# single_LED_driver.net
KiCad netlist of a schematic drawn in EAGLE
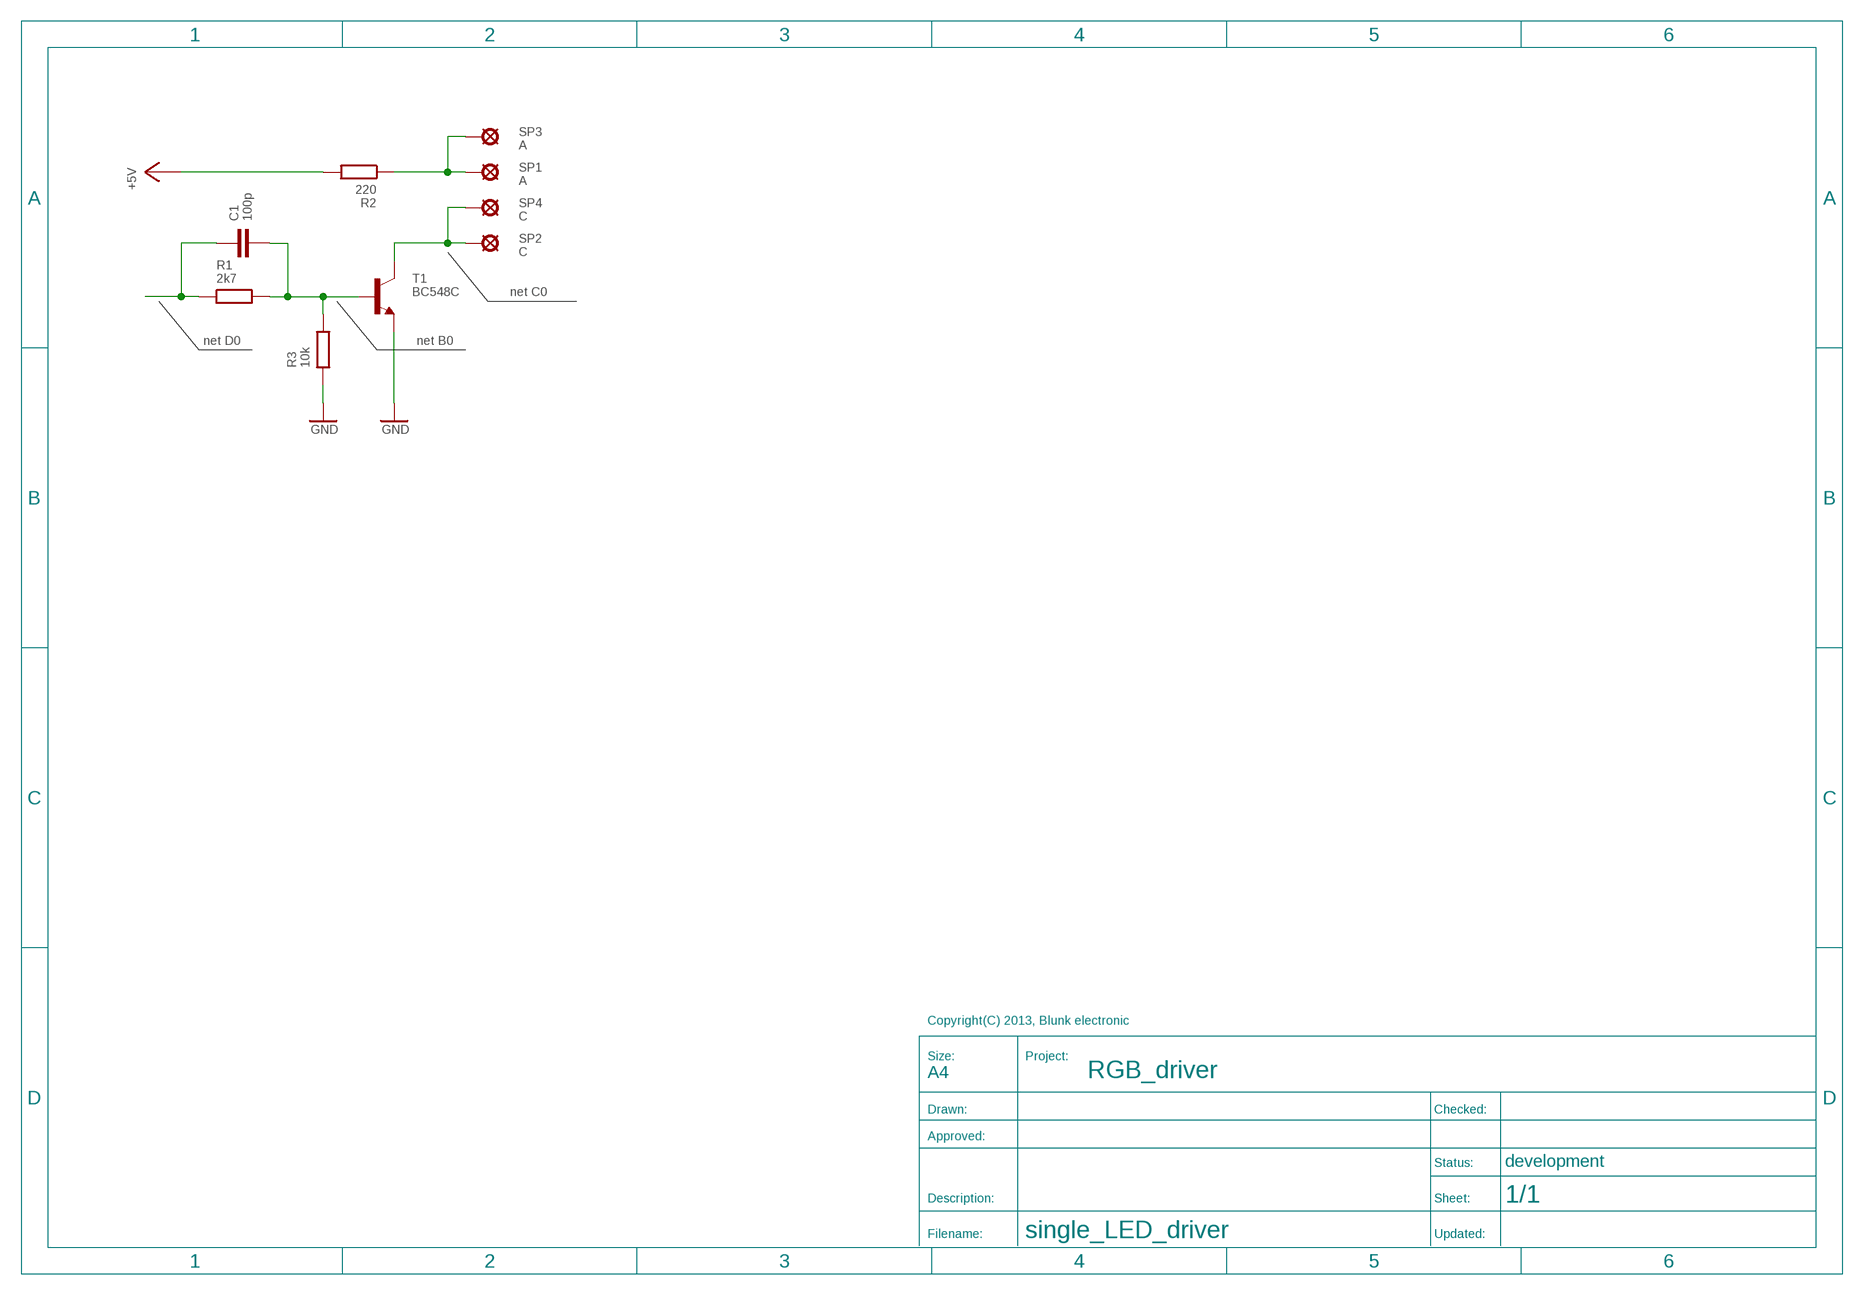
[diagram p0: schematic, sheet 1]

(export (version "E")
  (design (tool "Eeschema 10.0.6"))
  (components
    (comp (ref "C1")
      (value "100p")
      (footprint "eagle-import:S_0805")
      (libsource (lib "eagle-import") (part "C_EU_S_0805"))
    )
    (comp (ref "R1")
      (value "2k7")
      (footprint "eagle-import:S_0805")
      (libsource (lib "eagle-import") (part "R_EU_S_0805"))
    )
    (comp (ref "R2")
      (value "220")
      (footprint "eagle-import:S_0805")
      (libsource (lib "eagle-import") (part "R_EU_S_0805"))
    )
    (comp (ref "R3")
      (value "10k")
      (footprint "eagle-import:S_0805")
      (libsource (lib "eagle-import") (part "R_EU_S_0805"))
    )
    (comp (ref "SP1")
      (value "A")
      (footprint "eagle-import:T_TEST_POINT_SMALL")
      (libsource (lib "eagle-import") (part "TEST_POINT-T-SMALL"))
    )
    (comp (ref "SP2")
      (value "C")
      (footprint "eagle-import:T_TEST_POINT_SMALL")
      (libsource (lib "eagle-import") (part "TEST_POINT-T-SMALL"))
    )
    (comp (ref "SP3")
      (value "A")
      (footprint "eagle-import:T_TEST_POINT_SMALL")
      (libsource (lib "eagle-import") (part "TEST_POINT-T-SMALL"))
    )
    (comp (ref "SP4")
      (value "C")
      (footprint "eagle-import:T_TEST_POINT_SMALL")
      (libsource (lib "eagle-import") (part "TEST_POINT-T-SMALL"))
    )
    (comp (ref "T1")
      (value "BC548C")
      (footprint "eagle-import:T_TO-92-CBE")
      (libsource (lib "eagle-import") (part "NPN"))
    )
  )
  (nets
    (net (code "1") (name "+5V") (class "Default")
      (node (ref "R2") (pin "2") (pinfunction "2_2") (pintype "passive"))
    )
    (net (code "2") (name "GND") (class "Default")
      (node (ref "R3") (pin "1") (pinfunction "1_1") (pintype "passive"))
      (node (ref "T1") (pin "E") (pinfunction "E_E") (pintype "passive"))
    )
    (net (code "3") (name "Net-(C1-Pad1)") (class "Default")
      (node (ref "C1") (pin "1") (pinfunction "1_1") (pintype "passive"))
      (node (ref "R1") (pin "1") (pinfunction "1_1") (pintype "passive"))
    )
    (net (code "4") (name "Net-(C1-Pad2)") (class "Default")
      (node (ref "C1") (pin "2") (pinfunction "2_2") (pintype "passive"))
      (node (ref "R1") (pin "2") (pinfunction "2_2") (pintype "passive"))
      (node (ref "R3") (pin "2") (pinfunction "2_2") (pintype "passive"))
      (node (ref "T1") (pin "B") (pinfunction "B_B") (pintype "passive"))
    )
    (net (code "5") (name "Net-(SP1-MP)") (class "Default")
      (node (ref "R2") (pin "1") (pinfunction "1_1") (pintype "passive"))
      (node (ref "SP1") (pin "1") (pinfunction "MP_1") (pintype "passive"))
      (node (ref "SP3") (pin "1") (pinfunction "MP_1") (pintype "passive"))
    )
    (net (code "6") (name "Net-(SP2-MP)") (class "Default")
      (node (ref "SP2") (pin "1") (pinfunction "MP_1") (pintype "passive"))
      (node (ref "SP4") (pin "1") (pinfunction "MP_1") (pintype "passive"))
      (node (ref "T1") (pin "C") (pinfunction "C_C") (pintype "passive"))
    )
  )
)
